# AD7173.net
KiCad netlist of a schematic drawn in EAGLE
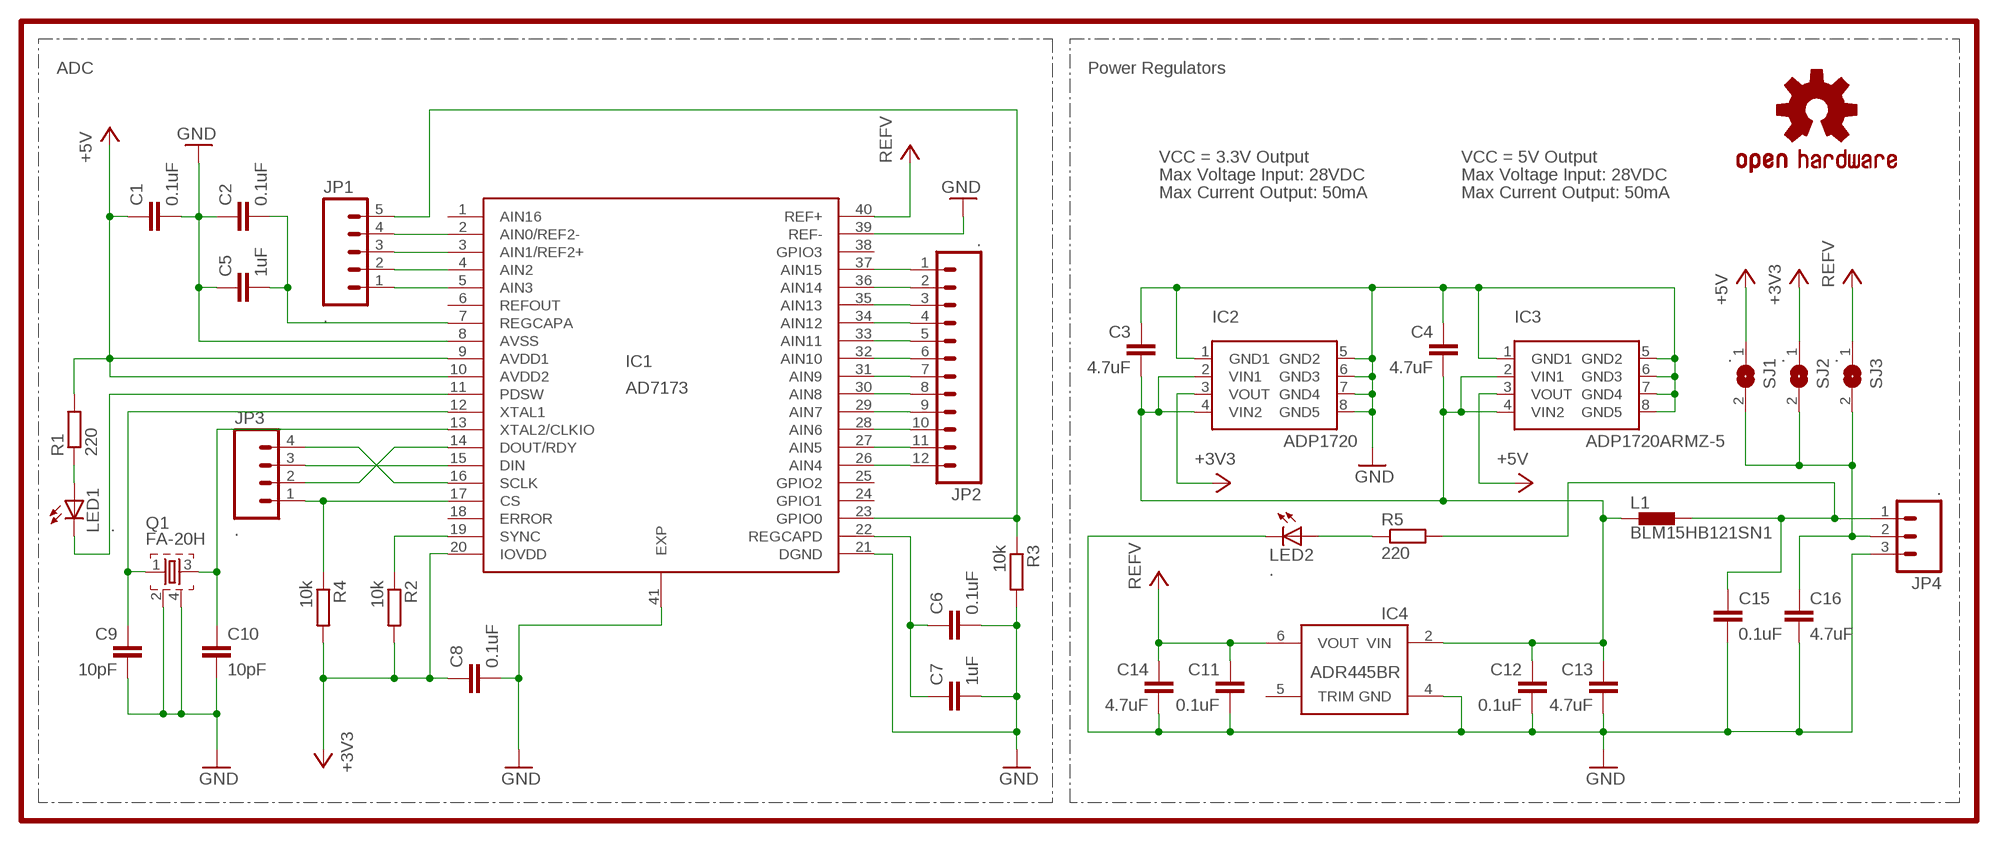
[diagram p0: schematic, sheet 1]

(export (version "E")
  (design (tool "Eeschema 10.0.6"))
  (components
    (comp (ref "C1")
      (value "0.1uF")
      (footprint "eagle-import:C0402")
      (libsource (lib "eagle-import") (part "C-EUC0402"))
    )
    (comp (ref "C2")
      (value "0.1uF")
      (footprint "eagle-import:C0402")
      (libsource (lib "eagle-import") (part "C-EUC0402"))
    )
    (comp (ref "C3")
      (value "4.7uF")
      (footprint "eagle-import:C0402")
      (libsource (lib "eagle-import") (part "C-EUC0402"))
    )
    (comp (ref "C4")
      (value "4.7uF")
      (footprint "eagle-import:C0402")
      (libsource (lib "eagle-import") (part "C-EUC0402"))
    )
    (comp (ref "C5")
      (value "1uF")
      (footprint "eagle-import:C0402")
      (libsource (lib "eagle-import") (part "C-EUC0402"))
    )
    (comp (ref "C6")
      (value "0.1uF")
      (footprint "eagle-import:C0402")
      (libsource (lib "eagle-import") (part "C-EUC0402"))
    )
    (comp (ref "C7")
      (value "1uF")
      (footprint "eagle-import:C0402")
      (libsource (lib "eagle-import") (part "C-EUC0402"))
    )
    (comp (ref "C8")
      (value "0.1uF")
      (footprint "eagle-import:C0402")
      (libsource (lib "eagle-import") (part "C-EUC0402"))
    )
    (comp (ref "C9")
      (value "10pF")
      (footprint "eagle-import:C0402")
      (libsource (lib "eagle-import") (part "C-EUC0402"))
    )
    (comp (ref "C10")
      (value "10pF")
      (footprint "eagle-import:C0402")
      (libsource (lib "eagle-import") (part "C-EUC0402"))
    )
    (comp (ref "C11")
      (value "0.1uF")
      (footprint "eagle-import:C0402")
      (libsource (lib "eagle-import") (part "C-EUC0402"))
    )
    (comp (ref "C12")
      (value "0.1uF")
      (footprint "eagle-import:C0402")
      (libsource (lib "eagle-import") (part "C-EUC0402"))
    )
    (comp (ref "C13")
      (value "4.7uF")
      (footprint "eagle-import:C0402")
      (libsource (lib "eagle-import") (part "C-EUC0402"))
    )
    (comp (ref "C14")
      (value "4.7uF")
      (footprint "eagle-import:C0402")
      (libsource (lib "eagle-import") (part "C-EUC0402"))
    )
    (comp (ref "C15")
      (value "0.1uF")
      (footprint "eagle-import:C0402")
      (libsource (lib "eagle-import") (part "C-EUC0402"))
    )
    (comp (ref "C16")
      (value "4.7uF")
      (footprint "eagle-import:C0402")
      (libsource (lib "eagle-import") (part "C-EUC0402"))
    )
    (comp (ref "IC1")
      (value "AD7173")
      (footprint "eagle-import:LFCSP_WQ6X6MM")
      (fields (field (name "MPN") "MRF24J40-I/ML"))
      (libsource (lib "eagle-import") (part "AD7173"))
    )
    (comp (ref "IC2")
      (value "ADP1720")
      (footprint "eagle-import:MSOP08")
      (libsource (lib "eagle-import") (part "POWER"))
    )
    (comp (ref "IC3")
      (value "ADP1720ARMZ-5")
      (footprint "eagle-import:MSOP08")
      (libsource (lib "eagle-import") (part "POWER"))
    )
    (comp (ref "IC4")
      (value "ADR445BR")
      (footprint "eagle-import:SO8")
      (libsource (lib "eagle-import") (part "ADR44R5B"))
    )
    (comp (ref "JP1")
      (value ".")
      (footprint "eagle-import:1X05")
      (libsource (lib "eagle-import") (part "M05PTH"))
    )
    (comp (ref "JP2")
      (value ".")
      (footprint "eagle-import:1X12")
      (libsource (lib "eagle-import") (part "M12PTH"))
    )
    (comp (ref "JP3")
      (value ".")
      (footprint "eagle-import:1X04")
      (libsource (lib "eagle-import") (part "M04PTH"))
    )
    (comp (ref "JP4")
      (value ".")
      (footprint "eagle-import:1X03")
      (libsource (lib "eagle-import") (part "M03PTH"))
    )
    (comp (ref "L1")
      (value "BLM15HB121SN1")
      (footprint "eagle-import:0402")
      (libsource (lib "eagle-import") (part "BLM15HB121SN1"))
    )
    (comp (ref "LED1")
      (value ".")
      (footprint "eagle-import:CHIP-LED0603")
      (libsource (lib "eagle-import") (part "LEDCHIP-LED0603"))
    )
    (comp (ref "LED2")
      (value ".")
      (footprint "eagle-import:CHIP-LED0603")
      (libsource (lib "eagle-import") (part "LEDCHIP-LED0603"))
    )
    (comp (ref "LOGO1")
      (value "OSHW-LOGOS")
      (footprint "eagle-import:OSHW-LOGO-S")
      (libsource (lib "eagle-import") (part "OSHW-LOGOS"))
    )
    (comp (ref "Q1")
      (value "FA-20H")
      (footprint "eagle-import:FA-20H")
      (libsource (lib "eagle-import") (part "FA-20H"))
    )
    (comp (ref "R1")
      (value "220")
      (footprint "eagle-import:R0402")
      (libsource (lib "eagle-import") (part "R-EU_R0402"))
    )
    (comp (ref "R2")
      (value "10k")
      (footprint "eagle-import:R0402")
      (libsource (lib "eagle-import") (part "R-EU_R0402"))
    )
    (comp (ref "R3")
      (value "10k")
      (footprint "eagle-import:R0402")
      (libsource (lib "eagle-import") (part "R-EU_R0402"))
    )
    (comp (ref "R4")
      (value "10k")
      (footprint "eagle-import:R0402")
      (libsource (lib "eagle-import") (part "R-EU_R0402"))
    )
    (comp (ref "R5")
      (value "220")
      (footprint "eagle-import:R0402")
      (libsource (lib "eagle-import") (part "R-EU_R0402"))
    )
    (comp (ref "SJ1") (value ".") (footprint "eagle-import:SJ") (libsource (lib "eagle-import") (part "SJ")))
    (comp (ref "SJ2") (value ".") (footprint "eagle-import:SJ") (libsource (lib "eagle-import") (part "SJ")))
    (comp (ref "SJ3") (value ".") (footprint "eagle-import:SJ") (libsource (lib "eagle-import") (part "SJ")))
  )
  (nets
    (net (code "1") (name "+3V3") (class "Default")
      (node (ref "C8") (pin "1") (pinfunction "1_1") (pintype "passive"))
      (node (ref "IC1") (pin "20") (pinfunction "IOVDD_20") (pintype "input"))
      (node (ref "IC2") (pin "3") (pinfunction "VOUT_3") (pintype "output"))
      (node (ref "R2") (pin "2") (pinfunction "2_2") (pintype "passive"))
      (node (ref "R4") (pin "2") (pinfunction "2_2") (pintype "passive"))
      (node (ref "SJ2") (pin "1") (pinfunction "1_1") (pintype "passive"))
    )
    (net (code "2") (name "+5V") (class "Default")
      (node (ref "C1") (pin "1") (pinfunction "1_1") (pintype "passive"))
      (node (ref "IC1") (pin "10") (pinfunction "AVDD2_10") (pintype "input"))
      (node (ref "IC1") (pin "9") (pinfunction "AVDD1_9") (pintype "input"))
      (node (ref "IC3") (pin "3") (pinfunction "VOUT_3") (pintype "output"))
      (node (ref "R1") (pin "2") (pinfunction "2_2") (pintype "passive"))
      (node (ref "SJ1") (pin "1") (pinfunction "1_1") (pintype "passive"))
    )
    (net (code "3") (name "GND") (class "Default")
      (node (ref "C1") (pin "2") (pinfunction "2_2") (pintype "passive"))
      (node (ref "C10") (pin "2") (pinfunction "2_2") (pintype "passive"))
      (node (ref "C11") (pin "2") (pinfunction "2_2") (pintype "passive"))
      (node (ref "C12") (pin "2") (pinfunction "2_2") (pintype "passive"))
      (node (ref "C13") (pin "2") (pinfunction "2_2") (pintype "passive"))
      (node (ref "C14") (pin "2") (pinfunction "2_2") (pintype "passive"))
      (node (ref "C15") (pin "2") (pinfunction "2_2") (pintype "passive"))
      (node (ref "C16") (pin "2") (pinfunction "2_2") (pintype "passive"))
      (node (ref "C2") (pin "1") (pinfunction "1_1") (pintype "passive"))
      (node (ref "C3") (pin "1") (pinfunction "1_1") (pintype "passive"))
      (node (ref "C4") (pin "1") (pinfunction "1_1") (pintype "passive"))
      (node (ref "C5") (pin "1") (pinfunction "1_1") (pintype "passive"))
      (node (ref "C6") (pin "2") (pinfunction "2_2") (pintype "passive"))
      (node (ref "C7") (pin "2") (pinfunction "2_2") (pintype "passive"))
      (node (ref "C8") (pin "2") (pinfunction "2_2") (pintype "passive"))
      (node (ref "C9") (pin "2") (pinfunction "2_2") (pintype "passive"))
      (node (ref "IC1") (pin "21") (pinfunction "DGND_21") (pintype "input"))
      (node (ref "IC1") (pin "39") (pinfunction "REF-_39") (pintype "input"))
      (node (ref "IC1") (pin "41") (pinfunction "EXP_41") (pintype "output"))
      (node (ref "IC1") (pin "8") (pinfunction "AVSS_8") (pintype "input"))
      (node (ref "IC2") (pin "1") (pinfunction "GND1_1") (pintype "power_in"))
      (node (ref "IC2") (pin "5") (pinfunction "GND2_5") (pintype "power_in"))
      (node (ref "IC2") (pin "6") (pinfunction "GND3_6") (pintype "power_in"))
      (node (ref "IC2") (pin "7") (pinfunction "GND4_7") (pintype "power_in"))
      (node (ref "IC2") (pin "8") (pinfunction "GND5_8") (pintype "power_in"))
      (node (ref "IC3") (pin "1") (pinfunction "GND1_1") (pintype "power_in"))
      (node (ref "IC3") (pin "5") (pinfunction "GND2_5") (pintype "power_in"))
      (node (ref "IC3") (pin "6") (pinfunction "GND3_6") (pintype "power_in"))
      (node (ref "IC3") (pin "7") (pinfunction "GND4_7") (pintype "power_in"))
      (node (ref "IC3") (pin "8") (pinfunction "GND5_8") (pintype "power_in"))
      (node (ref "IC4") (pin "4") (pinfunction "GND_4") (pintype "power_in"))
      (node (ref "JP4") (pin "3") (pinfunction "3_3") (pintype "passive"))
      (node (ref "LED2") (pin "C") (pinfunction "C_C") (pintype "passive"))
      (node (ref "Q1") (pin "2") (pinfunction "2_2") (pintype "passive"))
      (node (ref "Q1") (pin "4") (pinfunction "4_4") (pintype "passive"))
      (node (ref "R3") (pin "2") (pinfunction "2_2") (pintype "passive"))
    )
    (net (code "4") (name "Net-(C15-Pad1)") (class "Default")
      (node (ref "C15") (pin "1") (pinfunction "1_1") (pintype "passive"))
      (node (ref "JP4") (pin "1") (pinfunction "1_1") (pintype "passive"))
      (node (ref "L1") (pin "2") (pinfunction "2_2") (pintype "passive"))
      (node (ref "R5") (pin "2") (pinfunction "2_2") (pintype "passive"))
    )
    (net (code "5") (name "Net-(C16-Pad1)") (class "Default")
      (node (ref "C16") (pin "1") (pinfunction "1_1") (pintype "passive"))
      (node (ref "JP4") (pin "2") (pinfunction "2_2") (pintype "passive"))
      (node (ref "SJ1") (pin "2") (pinfunction "2_2") (pintype "passive"))
      (node (ref "SJ2") (pin "2") (pinfunction "2_2") (pintype "passive"))
      (node (ref "SJ3") (pin "2") (pinfunction "2_2") (pintype "passive"))
    )
    (net (code "6") (name "Net-(IC1-AIN0{slash}REF2-)") (class "Default")
      (node (ref "IC1") (pin "2") (pinfunction "AIN0/REF2-_2") (pintype "input"))
      (node (ref "JP1") (pin "4") (pinfunction "4_4") (pintype "passive"))
    )
    (net (code "7") (name "Net-(IC1-AIN1{slash}REF2+)") (class "Default")
      (node (ref "IC1") (pin "3") (pinfunction "AIN1/REF2+_3") (pintype "input"))
      (node (ref "JP1") (pin "3") (pinfunction "3_3") (pintype "passive"))
    )
    (net (code "8") (name "Net-(IC1-AIN2)") (class "Default")
      (node (ref "IC1") (pin "4") (pinfunction "AIN2_4") (pintype "input"))
      (node (ref "JP1") (pin "2") (pinfunction "2_2") (pintype "passive"))
    )
    (net (code "9") (name "Net-(IC1-AIN3)") (class "Default")
      (node (ref "IC1") (pin "5") (pinfunction "AIN3_5") (pintype "input"))
      (node (ref "JP1") (pin "1") (pinfunction "1_1") (pintype "passive"))
    )
    (net (code "10") (name "Net-(IC1-AIN4)") (class "Default")
      (node (ref "IC1") (pin "26") (pinfunction "AIN4_26") (pintype "input"))
      (node (ref "JP2") (pin "12") (pinfunction "12_12") (pintype "passive"))
    )
    (net (code "11") (name "Net-(IC1-AIN5)") (class "Default")
      (node (ref "IC1") (pin "27") (pinfunction "AIN5_27") (pintype "input"))
      (node (ref "JP2") (pin "11") (pinfunction "11_11") (pintype "passive"))
    )
    (net (code "12") (name "Net-(IC1-AIN6)") (class "Default")
      (node (ref "IC1") (pin "28") (pinfunction "AIN6_28") (pintype "input"))
      (node (ref "JP2") (pin "10") (pinfunction "10_10") (pintype "passive"))
    )
    (net (code "13") (name "Net-(IC1-AIN7)") (class "Default")
      (node (ref "IC1") (pin "29") (pinfunction "AIN7_29") (pintype "input"))
      (node (ref "JP2") (pin "9") (pinfunction "9_9") (pintype "passive"))
    )
    (net (code "14") (name "Net-(IC1-AIN8)") (class "Default")
      (node (ref "IC1") (pin "30") (pinfunction "AIN8_30") (pintype "input"))
      (node (ref "JP2") (pin "8") (pinfunction "8_8") (pintype "passive"))
    )
    (net (code "15") (name "Net-(IC1-AIN9)") (class "Default")
      (node (ref "IC1") (pin "31") (pinfunction "AIN9_31") (pintype "input"))
      (node (ref "JP2") (pin "7") (pinfunction "7_7") (pintype "passive"))
    )
    (net (code "16") (name "Net-(IC1-AIN10)") (class "Default")
      (node (ref "IC1") (pin "32") (pinfunction "AIN10_32") (pintype "input"))
      (node (ref "JP2") (pin "6") (pinfunction "6_6") (pintype "passive"))
    )
    (net (code "17") (name "Net-(IC1-AIN11)") (class "Default")
      (node (ref "IC1") (pin "33") (pinfunction "AIN11_33") (pintype "input"))
      (node (ref "JP2") (pin "5") (pinfunction "5_5") (pintype "passive"))
    )
    (net (code "18") (name "Net-(IC1-AIN12)") (class "Default")
      (node (ref "IC1") (pin "34") (pinfunction "AIN12_34") (pintype "input"))
      (node (ref "JP2") (pin "4") (pinfunction "4_4") (pintype "passive"))
    )
    (net (code "19") (name "Net-(IC1-AIN13)") (class "Default")
      (node (ref "IC1") (pin "35") (pinfunction "AIN13_35") (pintype "input"))
      (node (ref "JP2") (pin "3") (pinfunction "3_3") (pintype "passive"))
    )
    (net (code "20") (name "Net-(IC1-AIN14)") (class "Default")
      (node (ref "IC1") (pin "36") (pinfunction "AIN14_36") (pintype "input"))
      (node (ref "JP2") (pin "2") (pinfunction "2_2") (pintype "passive"))
    )
    (net (code "21") (name "Net-(IC1-AIN15)") (class "Default")
      (node (ref "IC1") (pin "37") (pinfunction "AIN15_37") (pintype "input"))
      (node (ref "JP2") (pin "1") (pinfunction "1_1") (pintype "passive"))
    )
    (net (code "22") (name "Net-(IC1-CS)") (class "Default")
      (node (ref "IC1") (pin "17") (pinfunction "CS_17") (pintype "input"))
      (node (ref "JP3") (pin "1") (pinfunction "1_1") (pintype "passive"))
      (node (ref "R4") (pin "1") (pinfunction "1_1") (pintype "passive"))
    )
    (net (code "23") (name "Net-(IC1-DIN)") (class "Default")
      (node (ref "IC1") (pin "15") (pinfunction "DIN_15") (pintype "input"))
      (node (ref "JP3") (pin "3") (pinfunction "3_3") (pintype "passive"))
    )
    (net (code "24") (name "Net-(IC1-DOUT{slash}RDY)") (class "Default")
      (node (ref "IC1") (pin "14") (pinfunction "DOUT/RDY_14") (pintype "output"))
      (node (ref "JP3") (pin "2") (pinfunction "2_2") (pintype "passive"))
    )
    (net (code "25") (name "Net-(IC1-GPIO0)") (class "Default")
      (node (ref "IC1") (pin "23") (pinfunction "GPIO0_23") (pintype "bidirectional"))
      (node (ref "JP1") (pin "5") (pinfunction "5_5") (pintype "passive"))
      (node (ref "R3") (pin "1") (pinfunction "1_1") (pintype "passive"))
    )
    (net (code "26") (name "Net-(IC1-PDSW)") (class "Default")
      (node (ref "IC1") (pin "11") (pinfunction "PDSW_11") (pintype "input"))
      (node (ref "LED1") (pin "C") (pinfunction "C_C") (pintype "passive"))
    )
    (net (code "27") (name "Net-(IC1-REGCAPA)") (class "Default")
      (node (ref "C2") (pin "2") (pinfunction "2_2") (pintype "passive"))
      (node (ref "C5") (pin "2") (pinfunction "2_2") (pintype "passive"))
      (node (ref "IC1") (pin "7") (pinfunction "REGCAPA_7") (pintype "input"))
    )
    (net (code "28") (name "Net-(IC1-REGCAPD)") (class "Default")
      (node (ref "C6") (pin "1") (pinfunction "1_1") (pintype "passive"))
      (node (ref "C7") (pin "1") (pinfunction "1_1") (pintype "passive"))
      (node (ref "IC1") (pin "22") (pinfunction "REGCAPD_22") (pintype "input"))
    )
    (net (code "29") (name "Net-(IC1-SCLK)") (class "Default")
      (node (ref "IC1") (pin "16") (pinfunction "SCLK_16") (pintype "input"))
      (node (ref "JP3") (pin "4") (pinfunction "4_4") (pintype "passive"))
    )
    (net (code "30") (name "Net-(IC1-SYNC)") (class "Default")
      (node (ref "IC1") (pin "19") (pinfunction "SYNC_19") (pintype "input"))
      (node (ref "R2") (pin "1") (pinfunction "1_1") (pintype "passive"))
    )
    (net (code "31") (name "Net-(IC1-XTAL1)") (class "Default")
      (node (ref "C9") (pin "1") (pinfunction "1_1") (pintype "passive"))
      (node (ref "IC1") (pin "12") (pinfunction "XTAL1_12") (pintype "input"))
      (node (ref "Q1") (pin "1") (pinfunction "1_1") (pintype "passive"))
    )
    (net (code "32") (name "Net-(IC1-XTAL2{slash}CLKIO)") (class "Default")
      (node (ref "C10") (pin "1") (pinfunction "1_1") (pintype "passive"))
      (node (ref "IC1") (pin "13") (pinfunction "XTAL2/CLKIO_13") (pintype "input"))
      (node (ref "Q1") (pin "3") (pinfunction "3_3") (pintype "passive"))
    )
    (net (code "33") (name "Net-(IC2-VIN1)") (class "Default")
      (node (ref "C12") (pin "1") (pinfunction "1_1") (pintype "passive"))
      (node (ref "C13") (pin "1") (pinfunction "1_1") (pintype "passive"))
      (node (ref "C3") (pin "2") (pinfunction "2_2") (pintype "passive"))
      (node (ref "C4") (pin "2") (pinfunction "2_2") (pintype "passive"))
      (node (ref "IC2") (pin "2") (pinfunction "VIN1_2") (pintype "input"))
      (node (ref "IC2") (pin "4") (pinfunction "VIN2_4") (pintype "input"))
      (node (ref "IC3") (pin "2") (pinfunction "VIN1_2") (pintype "input"))
      (node (ref "IC3") (pin "4") (pinfunction "VIN2_4") (pintype "input"))
      (node (ref "IC4") (pin "2") (pinfunction "VIN_2") (pintype "power_in"))
      (node (ref "L1") (pin "1") (pinfunction "1_1") (pintype "passive"))
    )
    (net (code "34") (name "Net-(LED1-PadA)") (class "Default")
      (node (ref "LED1") (pin "A") (pinfunction "A_A") (pintype "passive"))
      (node (ref "R1") (pin "1") (pinfunction "1_1") (pintype "passive"))
    )
    (net (code "35") (name "Net-(LED2-PadA)") (class "Default")
      (node (ref "LED2") (pin "A") (pinfunction "A_A") (pintype "passive"))
      (node (ref "R5") (pin "1") (pinfunction "1_1") (pintype "passive"))
    )
    (net (code "36") (name "REFV") (class "Default")
      (node (ref "C11") (pin "1") (pinfunction "1_1") (pintype "passive"))
      (node (ref "C14") (pin "1") (pinfunction "1_1") (pintype "passive"))
      (node (ref "IC1") (pin "40") (pinfunction "REF+_40") (pintype "input"))
      (node (ref "IC4") (pin "6") (pinfunction "VOUT_6") (pintype "bidirectional"))
      (node (ref "SJ3") (pin "1") (pinfunction "1_1") (pintype "passive"))
    )
    (net (code "37") (name "unconnected-(IC1-AIN16-Pad1)") (class "Default")
      (node (ref "IC1") (pin "1") (pinfunction "AIN16_1") (pintype "input"))
    )
    (net (code "38") (name "unconnected-(IC1-ERROR-Pad18)") (class "Default")
      (node (ref "IC1") (pin "18") (pinfunction "ERROR_18") (pintype "input"))
    )
    (net (code "39") (name "unconnected-(IC1-GPIO1-Pad24)") (class "Default")
      (node (ref "IC1") (pin "24") (pinfunction "GPIO1_24") (pintype "bidirectional"))
    )
    (net (code "40") (name "unconnected-(IC1-GPIO2-Pad25)") (class "Default")
      (node (ref "IC1") (pin "25") (pinfunction "GPIO2_25") (pintype "bidirectional"))
    )
    (net (code "41") (name "unconnected-(IC1-GPIO3-Pad38)") (class "Default")
      (node (ref "IC1") (pin "38") (pinfunction "GPIO3_38") (pintype "bidirectional"))
    )
    (net (code "42") (name "unconnected-(IC1-REFOUT-Pad6)") (class "Default")
      (node (ref "IC1") (pin "6") (pinfunction "REFOUT_6") (pintype "output"))
    )
    (net (code "43") (name "unconnected-(IC4-TRIM-Pad5)") (class "Default")
      (node (ref "IC4") (pin "5") (pinfunction "TRIM_5") (pintype "bidirectional"))
    )
  )
)
